# USB.net
KiCad netlist of a schematic drawn in Altium Designer
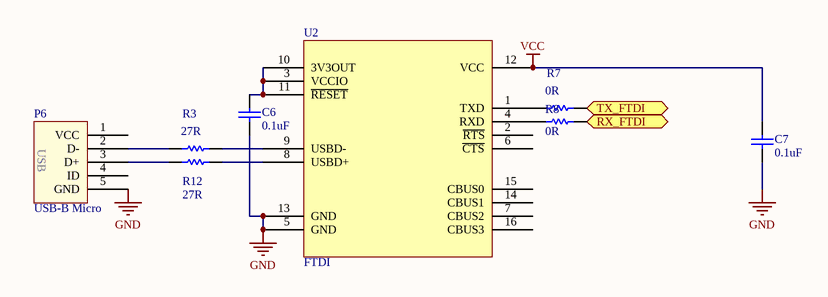
[diagram p0: USB.SchDoc]

(export (version "E")
  (design (tool "Eeschema 10.0.6"))
  (components
    (comp (ref "C6")
      (value "0.1uF")
      (footprint "0805")
      (description "Chip Capacitor")
      (fields (field (name "Comment") "Cap"))
      (libsource (lib "RCL") (part "Capacitor"))
    )
    (comp (ref "C7")
      (value "0.1uF")
      (footprint "0805")
      (description "Chip Capacitor")
      (fields (field (name "Comment") "Cap"))
      (libsource (lib "RCL") (part "Capacitor"))
    )
    (comp (ref "P6")
      (value "USB-B Micro")
      (footprint "USB B Micro WM14338CT-ND")
      (description "USB-B SMT Connector")
      (fields
        (field (name "DIGI-KEY PART NO.") "WM14338CT-ND")
        (field (name "MANUFACTURER PART NO.") "0476100001")
      )
      (libsource (lib "Connectors") (part "USB-B Micro 4 Pad"))
    )
    (comp (ref "R3")
      (value "27R")
      (footprint "0805")
      (description "Resistor")
      (fields (field (name "Comment") "Res1") (field (name "PUBLISHER") "Altium Limited"))
      (libsource (lib "Miscellaneous Devices") (part "Res1"))
    )
    (comp (ref "R7")
      (value "0R")
      (footprint "0805")
      (description "Resistor")
      (fields (field (name "Comment") "Res1") (field (name "PUBLISHER") "Altium Limited"))
      (libsource (lib "Miscellaneous Devices") (part "Res1"))
    )
    (comp (ref "R8")
      (value "0R")
      (footprint "0805")
      (description "Resistor")
      (fields (field (name "Comment") "Res1") (field (name "PUBLISHER") "Altium Limited"))
      (libsource (lib "Miscellaneous Devices") (part "Res1"))
    )
    (comp (ref "R12")
      (value "27R")
      (footprint "0805")
      (description "Resistor")
      (fields (field (name "Comment") "Res1") (field (name "PUBLISHER") "Altium Limited"))
      (libsource (lib "Miscellaneous Devices") (part "Res1"))
    )
    (comp (ref "U2")
      (value "FTDI")
      (footprint "FTDI_SSOP_16")
      (description "USB-UART Converter")
      (fields
        (field (name "DIGI-KEY PART NO.") "768-1135-1-ND")
        (field (name "MANUFACTURER PART NO.") "FT230XS-U")
      )
      (libsource (lib "Microcontroller-Related") (part "FTDI"))
    )
  )
  (nets
    (net (code "1") (name "/RX_FTDI") (class "Default")
      (node (ref "R8") (pin "1") (pinfunction "1_1") (pintype "passive"))
    )
    (net (code "2") (name "/TX_FTDI") (class "Default")
      (node (ref "R7") (pin "2") (pinfunction "2_2") (pintype "passive"))
    )
    (net (code "3") (name "GND") (class "Default")
      (node (ref "C6") (pin "1") (pinfunction "1_1") (pintype "passive"))
      (node (ref "C7") (pin "1") (pinfunction "1_1") (pintype "passive"))
      (node (ref "P6") (pin "5") (pinfunction "GND_5") (pintype "passive"))
      (node (ref "U2") (pin "13") (pinfunction "GND_13") (pintype "passive"))
      (node (ref "U2") (pin "5") (pinfunction "GND_5") (pintype "passive"))
    )
    (net (code "4") (name "Net-(P6-D+)") (class "Default")
      (node (ref "P6") (pin "3") (pinfunction "D+_3") (pintype "passive"))
      (node (ref "R12") (pin "1") (pinfunction "1_1") (pintype "passive"))
    )
    (net (code "5") (name "Net-(P6-D-)") (class "Default")
      (node (ref "P6") (pin "2") (pinfunction "D-_2") (pintype "passive"))
      (node (ref "R3") (pin "1") (pinfunction "1_1") (pintype "passive"))
    )
    (net (code "6") (name "Net-(U2-3V3OUT)") (class "Default")
      (node (ref "C6") (pin "2") (pinfunction "2_2") (pintype "passive"))
      (node (ref "U2") (pin "10") (pinfunction "3V3OUT_10") (pintype "passive"))
      (node (ref "U2") (pin "11") (pinfunction "~{RESET}_11") (pintype "passive"))
      (node (ref "U2") (pin "3") (pinfunction "VCCIO_3") (pintype "passive"))
    )
    (net (code "7") (name "Net-(U2-RXD)") (class "Default")
      (node (ref "R8") (pin "2") (pinfunction "2_2") (pintype "passive"))
      (node (ref "U2") (pin "4") (pinfunction "RXD_4") (pintype "passive"))
    )
    (net (code "8") (name "Net-(U2-TXD)") (class "Default")
      (node (ref "R7") (pin "1") (pinfunction "1_1") (pintype "passive"))
      (node (ref "U2") (pin "1") (pinfunction "TXD_1") (pintype "passive"))
    )
    (net (code "9") (name "Net-(U2-USBD+)") (class "Default")
      (node (ref "R12") (pin "2") (pinfunction "2_2") (pintype "passive"))
      (node (ref "U2") (pin "8") (pinfunction "USBD+_8") (pintype "passive"))
    )
    (net (code "10") (name "Net-(U2-USBD-)") (class "Default")
      (node (ref "R3") (pin "2") (pinfunction "2_2") (pintype "passive"))
      (node (ref "U2") (pin "9") (pinfunction "USBD-_9") (pintype "passive"))
    )
    (net (code "11") (name "VCC") (class "Default")
      (node (ref "C7") (pin "2") (pinfunction "2_2") (pintype "passive"))
      (node (ref "U2") (pin "12") (pinfunction "VCC_12") (pintype "passive"))
    )
    (net (code "12") (name "unconnected-(P6-ID-Pad4)") (class "Default")
      (node (ref "P6") (pin "4") (pinfunction "ID_4") (pintype "passive"))
    )
    (net (code "13") (name "unconnected-(P6-VCC-Pad1)") (class "Default")
      (node (ref "P6") (pin "1") (pinfunction "VCC_1") (pintype "passive"))
    )
    (net (code "14") (name "unconnected-(U2-CBUS0-Pad15)") (class "Default")
      (node (ref "U2") (pin "15") (pinfunction "CBUS0_15") (pintype "passive"))
    )
    (net (code "15") (name "unconnected-(U2-CBUS1-Pad14)") (class "Default")
      (node (ref "U2") (pin "14") (pinfunction "CBUS1_14") (pintype "passive"))
    )
    (net (code "16") (name "unconnected-(U2-CBUS2-Pad7)") (class "Default")
      (node (ref "U2") (pin "7") (pinfunction "CBUS2_7") (pintype "passive"))
    )
    (net (code "17") (name "unconnected-(U2-CBUS3-Pad16)") (class "Default")
      (node (ref "U2") (pin "16") (pinfunction "CBUS3_16") (pintype "passive"))
    )
    (net (code "18") (name "unconnected-(U2-~{CTS}-Pad6)") (class "Default")
      (node (ref "U2") (pin "6") (pinfunction "~{CTS}_6") (pintype "passive"))
    )
    (net (code "19") (name "unconnected-(U2-~{RTS}-Pad2)") (class "Default")
      (node (ref "U2") (pin "2") (pinfunction "~{RTS}_2") (pintype "passive"))
    )
  )
)
